# USB.net
KiCad netlist of a schematic drawn in Altium Designer
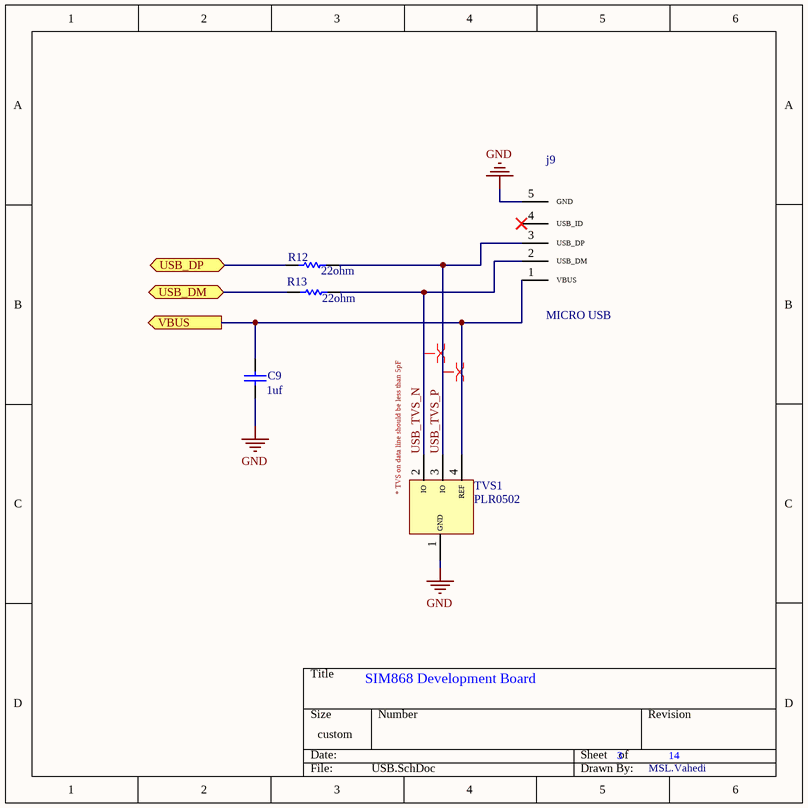
[diagram p0: USB.SchDoc]

(export (version "E")
  (design (tool "Eeschema 10.0.6"))
  (components
    (comp (ref "C9")
      (value "1uf")
      (footprint "CAP0805")
      (description "Capacitor")
      (fields (field (name "PUBLISHER") "Altium Limited"))
      (libsource (lib "Miscellaneous Devices") (part "Cap"))
    )
    (comp (ref "j9")
      (value "MICRO USB")
      (footprint "Micro_USB")
      (libsource (lib "Schlib1") (part "MICRO USB"))
    )
    (comp (ref "R12")
      (value "22ohm")
      (footprint "RES0805")
      (fields (field (name "PUBLISHER") "Altium Limited"))
      (libsource (lib "Miscellaneous Devices") (part "Res1"))
    )
    (comp (ref "R13")
      (value "22ohm")
      (footprint "RES0805")
      (fields (field (name "PUBLISHER") "Altium Limited"))
      (libsource (lib "Miscellaneous Devices") (part "Res1"))
    )
    (comp (ref "TVS1") (value "PLR0502") (footprint "PLR0502") (libsource (lib "PLR0502") (part "PLR0502")))
  )
  (nets
    (net (code "1") (name "/USB_DM") (class "Default")
      (node (ref "R13") (pin "1") (pinfunction "1_1") (pintype "passive"))
    )
    (net (code "2") (name "/USB_DP") (class "Default")
      (node (ref "R12") (pin "1") (pinfunction "1_1") (pintype "passive"))
    )
    (net (code "3") (name "/USB_TVS_N") (class "Default")
      (node (ref "R13") (pin "2") (pinfunction "2_2") (pintype "passive"))
      (node (ref "TVS1") (pin "2") (pinfunction "IO_2") (pintype "passive"))
      (node (ref "j9") (pin "2") (pinfunction "USB_DM_2") (pintype "passive"))
    )
    (net (code "4") (name "/USB_TVS_P") (class "Default")
      (node (ref "R12") (pin "2") (pinfunction "2_2") (pintype "passive"))
      (node (ref "TVS1") (pin "3") (pinfunction "IO_3") (pintype "passive"))
      (node (ref "j9") (pin "3") (pinfunction "USB_DP_3") (pintype "passive"))
    )
    (net (code "5") (name "/VBUS") (class "Default")
      (node (ref "C9") (pin "2") (pinfunction "2_2") (pintype "passive"))
      (node (ref "TVS1") (pin "4") (pinfunction "REF_4") (pintype "passive"))
      (node (ref "j9") (pin "1") (pinfunction "VBUS_1") (pintype "passive"))
    )
    (net (code "6") (name "GND") (class "Default")
      (node (ref "C9") (pin "1") (pinfunction "1_1") (pintype "passive"))
      (node (ref "TVS1") (pin "1") (pinfunction "GND_1") (pintype "passive"))
      (node (ref "j9") (pin "5") (pinfunction "GND_5") (pintype "passive"))
    )
    (net (code "7") (name "unconnected-(j9-USB_ID-Pad4)") (class "Default")
      (node (ref "j9") (pin "4") (pinfunction "USB_ID_4") (pintype "passive+no_connect"))
    )
  )
)
